# watch.net
KiCad netlist of a schematic drawn in Altium Designer
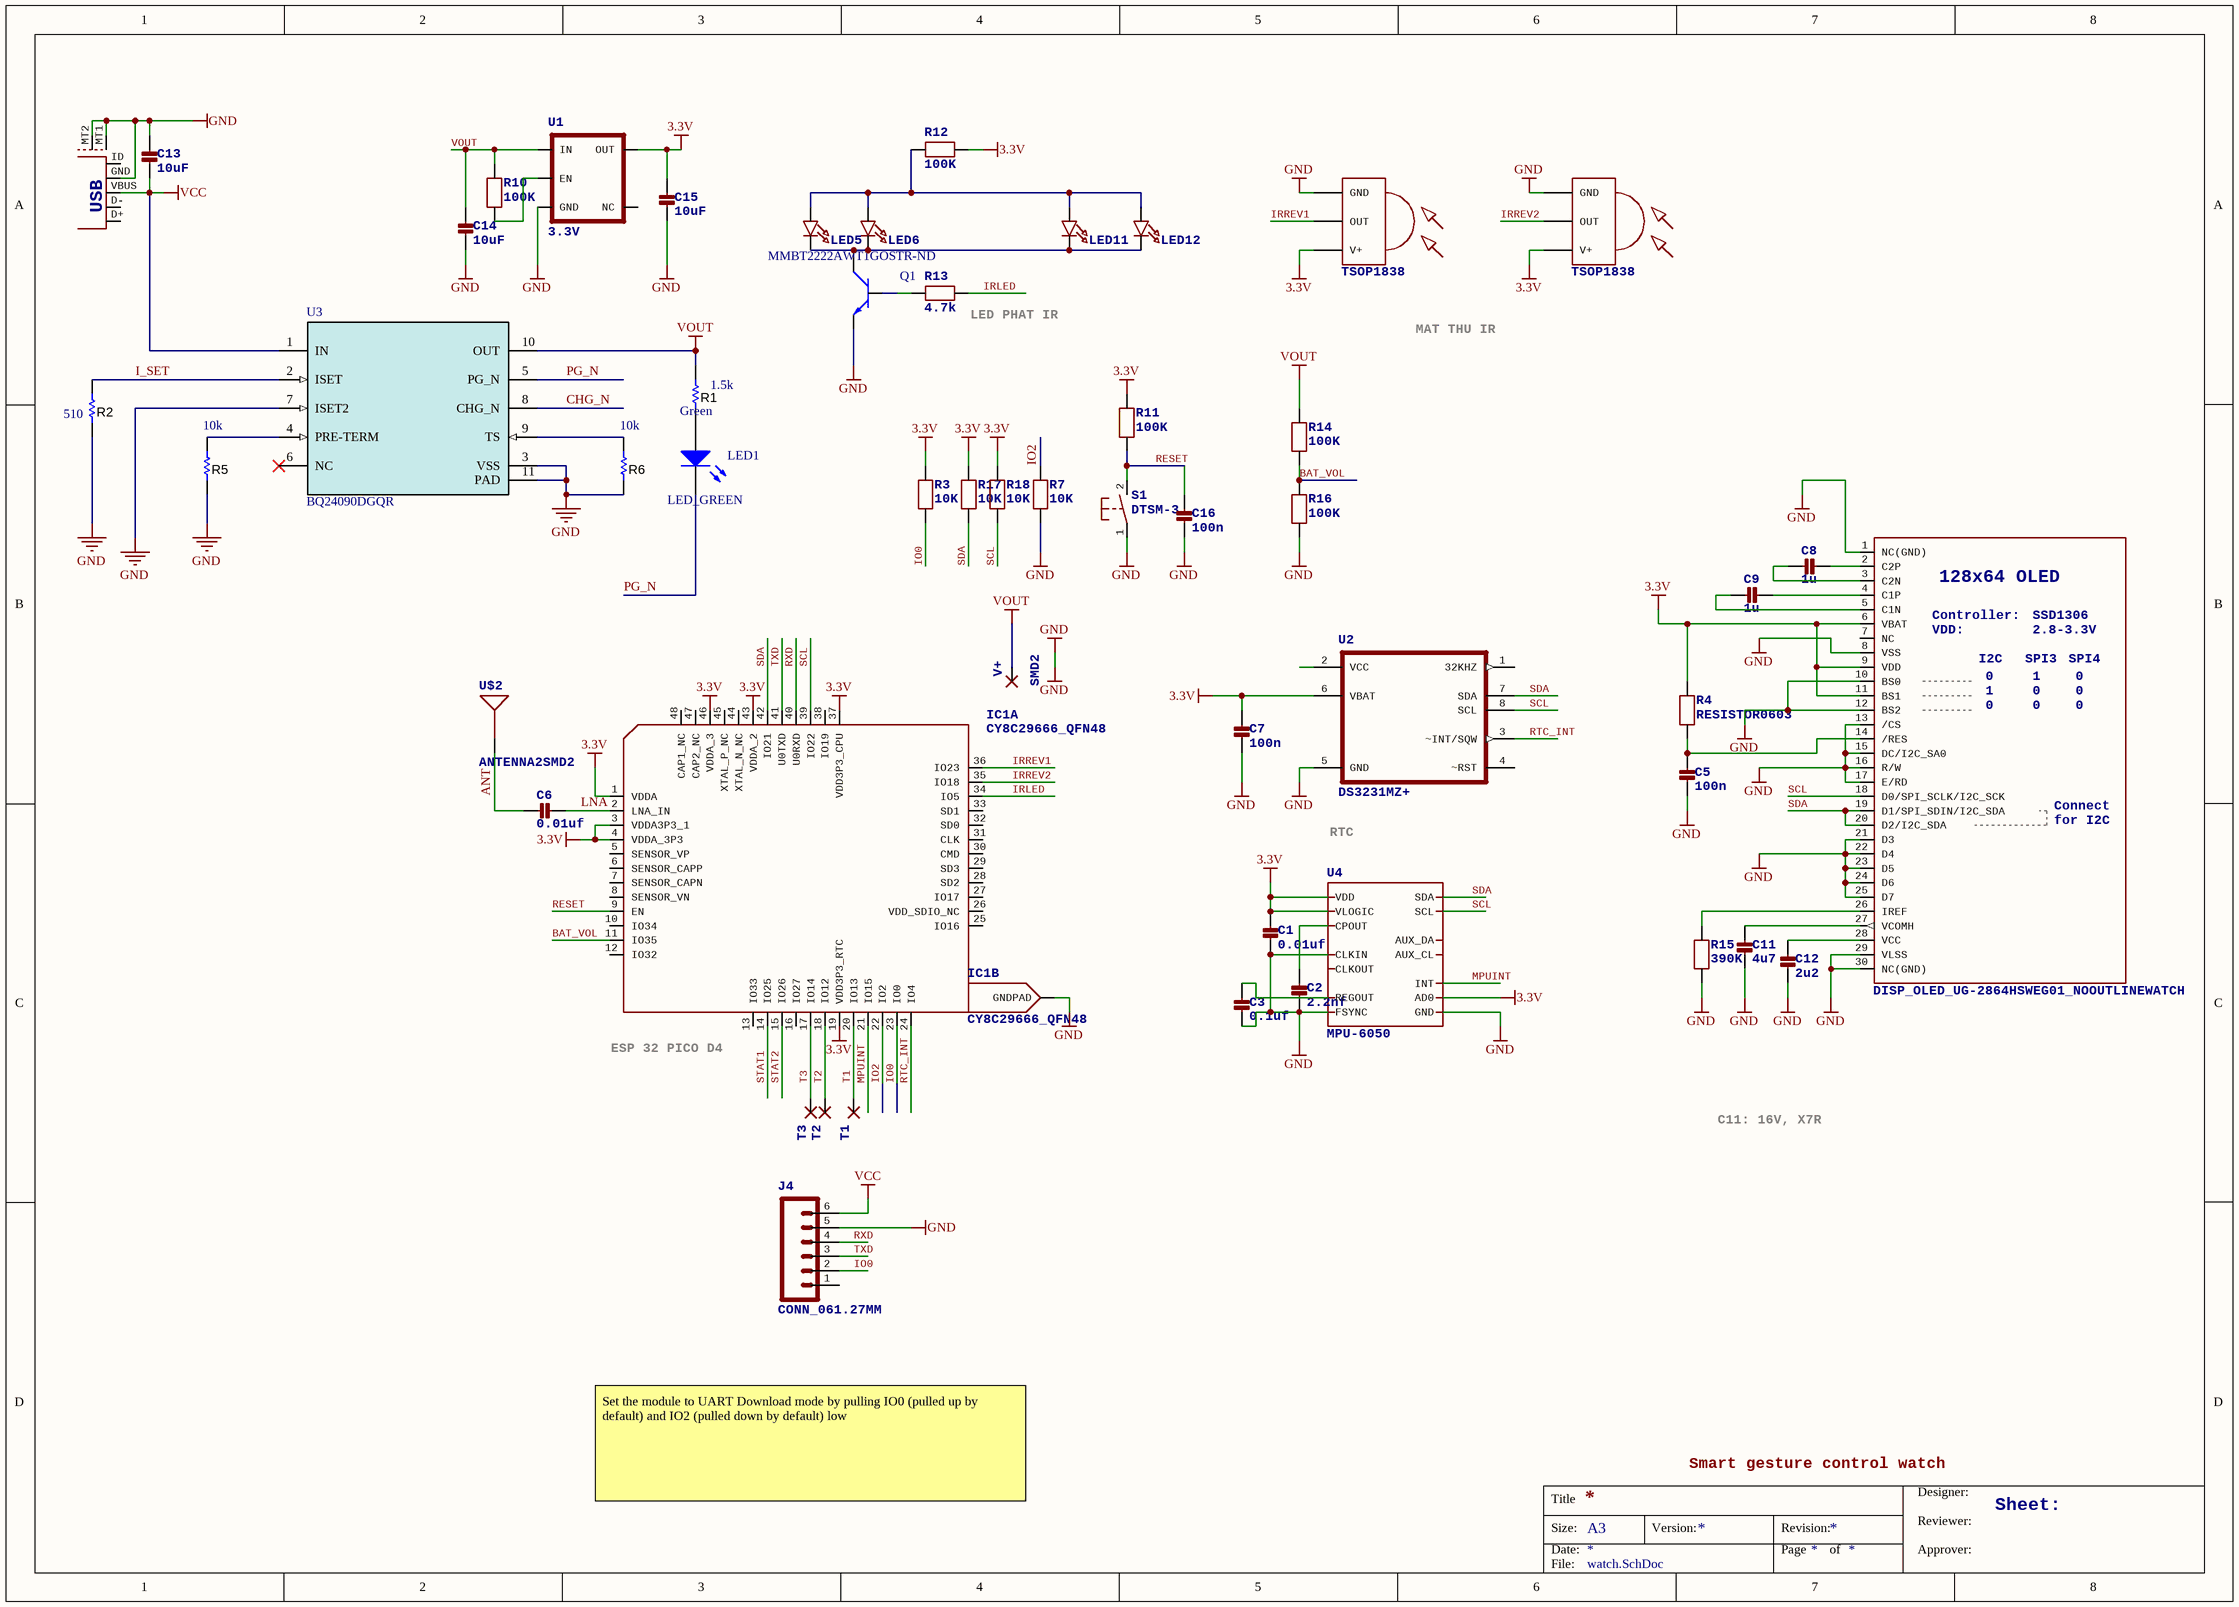
[diagram p0: watch.SchDoc]

(export (version "E")
  (design (tool "Eeschema 10.0.6"))
  (components
    (comp (ref "C1") (value "0.01uf") (footprint "0603") (libsource (lib "") (part "CAP_CERAMIC0603_2")))
    (comp (ref "C2")
      (value "2.2nf")
      (footprint "0603")
      (libsource (lib "microbuilder") (part "CAP_CERAMIC0603"))
    )
    (comp (ref "C3") (value "0.1uf") (footprint "0603") (libsource (lib "") (part "CAP_CERAMIC0603_2")))
    (comp (ref "C5")
      (value "100n")
      (footprint "0603")
      (libsource (lib "microbuilder") (part "CAP_CERAMIC0603"))
    )
    (comp (ref "C6") (value "0.01uf") (footprint "0603") (libsource (lib "") (part "CAP_CERAMIC0603_1")))
    (comp (ref "C7")
      (value "100n")
      (footprint "0603")
      (libsource (lib "microbuilder") (part "CAP_CERAMIC0603"))
    )
    (comp (ref "C8") (value "1u") (footprint "0603") (libsource (lib "") (part "CAP_CERAMIC0603_1")))
    (comp (ref "C9") (value "1u") (footprint "0603") (libsource (lib "") (part "CAP_CERAMIC0603_1")))
    (comp (ref "C11")
      (value "4u7")
      (footprint "0603")
      (libsource (lib "microbuilder") (part "CAP_CERAMIC0603"))
    )
    (comp (ref "C12")
      (value "2u2")
      (footprint "0603")
      (libsource (lib "microbuilder") (part "CAP_CERAMIC0603"))
    )
    (comp (ref "C13")
      (value "10uF")
      (footprint "0603")
      (libsource (lib "microbuilder") (part "CAP_CERAMIC0603"))
    )
    (comp (ref "C14")
      (value "10uF")
      (footprint "0603")
      (libsource (lib "microbuilder") (part "CAP_CERAMIC0603"))
    )
    (comp (ref "C15")
      (value "10uF")
      (footprint "0603")
      (libsource (lib "microbuilder") (part "CAP_CERAMIC0603"))
    )
    (comp (ref "C16")
      (value "100n")
      (footprint "0603")
      (libsource (lib "microbuilder") (part "CAP_CERAMIC0603"))
    )
    (comp (ref "IC1")
      (value "CY8C29666_QFN48")
      (footprint "QFN48")
      (libsource (lib "watch") (part "CY8C29666_QFN48"))
    )
    (comp (ref "J4")
      (value "CONN_061.27MM")
      (footprint "1X06_1.27MM")
      (libsource (lib "SparkFun-Connectors") (part "CONN_061.27MM"))
    )
    (comp (ref "LED1")
      (value "LED_GREEN")
      (footprint "led0603")
      (description "Typical INFRARED GaAs LED")
      (fields
        (field (name "MANUFACTURER") "Lite-On Inc.")
        (field (name "MANUFACTURER PART NUMBER") "LTST-C191KGKT")
        (field (name "COLOR") "Green")
      )
      (libsource (lib "BBiQ_LIB") (part "LED_GREEN"))
    )
    (comp (ref "LED5")
      (value "LED0805")
      (footprint "CHIPLED_0805")
      (libsource (lib "watch") (part "LED0805"))
    )
    (comp (ref "LED6")
      (value "LED0805")
      (footprint "CHIPLED_0805")
      (libsource (lib "watch") (part "LED0805"))
    )
    (comp (ref "LED11")
      (value "LED0805")
      (footprint "CHIPLED_0805")
      (libsource (lib "watch") (part "LED0805"))
    )
    (comp (ref "LED12")
      (value "LED0805")
      (footprint "CHIPLED_0805")
      (libsource (lib "watch") (part "LED0805"))
    )
    (comp (ref "OLED1")
      (value "DISP_OLED_UG-2864HSWEG01_NOOUTLINEWATCH")
      (footprint "UG-2864HSWEG01_1.3_WRAPAROUND_WATCH")
      (fields
        (field (name "128X64OLED") "128x64 OLED")
        (field (name "I2C") "I2C")
        (field (name "SPI3") "SPI3")
        (field (name "0") "0")
        (field (name "0_1") "0")
        (field (name "0_2") "0")
        (field (name "0_3") "0")
        (field (name "1") "1")
        (field (name "1_1") "1")
        (field (name "CONNECT") "Connect")
        (field (name "FORI2C") "for I2C")
        (field (name "CONTROLLER") "Controller:")
        (field (name "SSD1306") "SSD1306")
        (field (name "VDD") "VDD:")
        (field (name "2.8-3.3V") "2.8-3.3V")
        (field (name "SPI4") "SPI4")
        (field (name "0_4") "0")
        (field (name "0_5") "0")
        (field (name "0_6") "0")
      )
      (libsource (lib "zak") (part "DISP_OLED_UG-2864HSWEG01_NOOUTLINEWATCH"))
    )
    (comp (ref "Q1")
      (value "MMBT2222A")
      (footprint "SOT-323")
      (description "NPN switching transistor  40V 600mA SOT23")
      (fields
        (field (name "SUPPLIER PART NUMBER 1") "MMBT2222AWT1GOSTR-ND")
        (field (name "MANUFACTURER") "ON Semiconductor")
        (field (name "MANUFACTURER PART NUMBER") "MMBT2222AWT1G")
      )
      (libsource (lib "BBiQ_LIB") (part "MMBT2222A"))
    )
    (comp (ref "R1")
      (value "~")
      (footprint "0603")
      (description "RES SMD 1.5K OHM 5% 1/10W 0603")
      (fields
        (field (name "MANUFACTURER") "Yageo")
        (field (name "MANUFACTURER PART NUMBER") "RC0603JR-071K5L")
        (field (name "RESISTANCE (OHMS)") "1.5k")
      )
      (libsource (lib "BBiQ_LIB") (part "RC0603JR-071K5L"))
    )
    (comp (ref "R2")
      (value "~")
      (footprint "0603")
      (description "RES SMD 510 OHM 5% 1/10W 0603")
      (fields
        (field (name "MANUFACTURER") "Yageo")
        (field (name "MANUFACTURER PART NUMBER") "RC0603JR-07510RL")
        (field (name "RESISTANCE (OHMS)") "510")
      )
      (libsource (lib "BBiQ_LIB") (part "RC0603JR-07510RL"))
    )
    (comp (ref "R3") (value "10K") (footprint "0603") (libsource (lib "microbuilder") (part "RESISTOR0603")))
    (comp (ref "R4")
      (value "RESISTOR0603")
      (footprint "0603")
      (libsource (lib "microbuilder") (part "RESISTOR0603"))
    )
    (comp (ref "R5")
      (value "~")
      (footprint "0603")
      (description "RES SMD 10K OHM 5% 1/10W 0603")
      (fields
        (field (name "MANUFACTURER") "Yageo")
        (field (name "MANUFACTURER PART NUMBER") "RC0603JR-0710KL")
        (field (name "RESISTANCE (OHMS)") "10k")
      )
      (libsource (lib "BBiQ_LIB") (part "RC0603JR-0710KL"))
    )
    (comp (ref "R6")
      (value "~")
      (footprint "0603")
      (description "RES SMD 10K OHM 5% 1/10W 0603")
      (fields
        (field (name "MANUFACTURER") "Yageo")
        (field (name "MANUFACTURER PART NUMBER") "RC0603JR-0710KL")
        (field (name "RESISTANCE (OHMS)") "10k")
      )
      (libsource (lib "BBiQ_LIB") (part "RC0603JR-0710KL"))
    )
    (comp (ref "R7") (value "10K") (footprint "0603") (libsource (lib "microbuilder") (part "RESISTOR0603")))
    (comp (ref "R10")
      (value "100K")
      (footprint "0603")
      (libsource (lib "microbuilder") (part "RESISTOR0603"))
    )
    (comp (ref "R11")
      (value "100K")
      (footprint "0603")
      (libsource (lib "microbuilder") (part "RESISTOR0603"))
    )
    (comp (ref "R12")
      (value "100K")
      (footprint "0603")
      (libsource (lib "microbuilder") (part "RESISTOR0603"))
    )
    (comp (ref "R13")
      (value "4.7k")
      (footprint "0603")
      (libsource (lib "microbuilder") (part "RESISTOR0603"))
    )
    (comp (ref "R14")
      (value "100K")
      (footprint "0603")
      (libsource (lib "microbuilder") (part "RESISTOR0603"))
    )
    (comp (ref "R15")
      (value "390K")
      (footprint "0603")
      (libsource (lib "microbuilder") (part "RESISTOR0603"))
    )
    (comp (ref "R16")
      (value "100K")
      (footprint "0603")
      (libsource (lib "microbuilder") (part "RESISTOR0603"))
    )
    (comp (ref "R17") (value "10K") (footprint "0603") (libsource (lib "microbuilder") (part "RESISTOR0603")))
    (comp (ref "R18") (value "10K") (footprint "0603") (libsource (lib "microbuilder") (part "RESISTOR0603")))
    (comp (ref "S1") (value "DTSM-3") (footprint "DTSM-3") (libsource (lib "switch-tact") (part "DTSM-3")))
    (comp (ref "T1")
      (value "SMD2")
      (footprint "SMD1,27-2,54")
      (description "SMD PAD")
      (libsource (lib "wirepad") (part "SMD2"))
    )
    (comp (ref "T2")
      (value "SMD2")
      (footprint "SMD1,27-2,54")
      (description "SMD PAD")
      (libsource (lib "wirepad") (part "SMD2"))
    )
    (comp (ref "T3")
      (value "SMD2")
      (footprint "SMD1,27-2,54")
      (description "SMD PAD")
      (libsource (lib "wirepad") (part "SMD2"))
    )
    (comp (ref "U$2")
      (value "ANTENNA2SMD2")
      (footprint "ANTENNA-CHIP3")
      (libsource (lib "SparkFun-RF") (part "ANTENNA2SMD2"))
    )
    (comp (ref "U$3")
      (value "TSOP1838")
      (footprint "TSOP18XX")
      (description "IR Receiver and Demodulator")
      (libsource (lib "tsop-1") (part "TSOP1838"))
    )
    (comp (ref "U$4")
      (value "TSOP1838")
      (footprint "TSOP18XX")
      (description "IR Receiver and Demodulator")
      (libsource (lib "tsop-1") (part "TSOP1838"))
    )
    (comp (ref "U1")
      (value "3.3V")
      (footprint "SOT23-5")
      (libsource (lib "SparkFun-IC-Power") (part "V_REG_AP2112K-3.3V"))
    )
    (comp (ref "U2")
      (value "DS3231MZ+")
      (footprint "SOIC8_150MIL_SMPAD")
      (libsource (lib "zak") (part "DS3231MZ+SMPAD"))
    )
    (comp (ref "U3")
      (value "BQ24090DGQR")
      (footprint "DGQ0010D_NV_N")
      (description "Single Cell Li-Ion and Li-Pol Battery Charger")
      (fields (field (name "MANUFACTURER") "Texas Instruments"))
      (libsource (lib "BBiQ_LIB") (part "BQ24090DGQR"))
    )
    (comp (ref "U4")
      (value "MPU-6050")
      (footprint "QFN.24.4X4")
      (libsource (lib "invensense") (part "MPU-6050"))
    )
    (comp (ref "USB1")
      (value "USB-MICROBLARGEPAD")
      (footprint "USB-MICROB_LARGEPAD")
      (fields (field (name "USB") "USB"))
      (libsource (lib "zak") (part "USB-MICROBLARGEPAD"))
    )
    (comp (ref "V+")
      (value "SMD2")
      (footprint "SMD1,27-2,54")
      (description "SMD PAD")
      (libsource (lib "wirepad") (part "SMD2"))
    )
  )
  (nets
    (net (code "1") (name "/ANT") (class "Default")
      (node (ref "C6") (pin "1") (pinfunction "P$1_1") (pintype "passive"))
      (node (ref "U$2") (pin "FEED") (pinfunction "SIGNAL_FEED") (pintype "passive"))
    )
    (net (code "2") (name "/BAT_VOL") (class "Default")
      (node (ref "IC1") (pin "11") (pinfunction "IO35_11") (pintype "passive"))
      (node (ref "R14") (pin "2") (pinfunction "2_2") (pintype "passive"))
      (node (ref "R16") (pin "1") (pinfunction "1_1") (pintype "passive"))
    )
    (net (code "3") (name "/CHG_N") (class "Default")
      (node (ref "U3") (pin "8") (pinfunction "CHG_N_8") (pintype "tri_state"))
    )
    (net (code "4") (name "/IO0") (class "Default")
      (node (ref "IC1") (pin "23") (pinfunction "IO0_23") (pintype "passive"))
      (node (ref "J4") (pin "2") (pinfunction "2_2") (pintype "passive"))
      (node (ref "R3") (pin "2") (pinfunction "2_2") (pintype "passive"))
    )
    (net (code "5") (name "/IO2") (class "Default")
      (node (ref "IC1") (pin "22") (pinfunction "IO2_22") (pintype "passive"))
      (node (ref "R7") (pin "1") (pinfunction "1_1") (pintype "passive"))
    )
    (net (code "6") (name "/IRLED") (class "Default")
      (node (ref "IC1") (pin "34") (pinfunction "IO5_34") (pintype "passive"))
      (node (ref "R13") (pin "1") (pinfunction "1_1") (pintype "passive"))
    )
    (net (code "7") (name "/IRREV1") (class "Default")
      (node (ref "IC1") (pin "36") (pinfunction "IO23_36") (pintype "passive"))
      (node (ref "U$4") (pin "OUT") (pinfunction "OUT_OUT") (pintype "passive"))
    )
    (net (code "8") (name "/IRREV2") (class "Default")
      (node (ref "IC1") (pin "35") (pinfunction "IO18_35") (pintype "passive"))
      (node (ref "U$3") (pin "OUT") (pinfunction "OUT_OUT") (pintype "passive"))
    )
    (net (code "9") (name "/I_SET") (class "Default")
      (node (ref "R2") (pin "2") (pinfunction "2_2") (pintype "passive"))
      (node (ref "U3") (pin "2") (pinfunction "ISET_2") (pintype "input"))
    )
    (net (code "10") (name "/LNA") (class "Default")
      (node (ref "C6") (pin "2") (pinfunction "P$2_2") (pintype "passive"))
      (node (ref "IC1") (pin "2") (pinfunction "LNA_IN_2") (pintype "passive"))
    )
    (net (code "11") (name "/MPUINT") (class "Default")
      (node (ref "IC1") (pin "21") (pinfunction "IO15_21") (pintype "passive"))
      (node (ref "U4") (pin "12") (pinfunction "INT_12") (pintype "passive"))
    )
    (net (code "12") (name "/PG_N") (class "Default")
      (node (ref "LED1") (pin "2") (pinfunction "K_2") (pintype "passive"))
      (node (ref "U3") (pin "5") (pinfunction "PG_N_5") (pintype "tri_state"))
    )
    (net (code "13") (name "/RESET") (class "Default")
      (node (ref "C16") (pin "1") (pinfunction "P$1_1") (pintype "passive"))
      (node (ref "IC1") (pin "9") (pinfunction "EN_9") (pintype "passive"))
      (node (ref "R11") (pin "1") (pinfunction "1_1") (pintype "passive"))
      (node (ref "S1") (pin "2") (pinfunction "2_2") (pintype "passive"))
    )
    (net (code "14") (name "/RTC_INT") (class "Default")
      (node (ref "IC1") (pin "24") (pinfunction "IO4_24") (pintype "passive"))
      (node (ref "U2") (pin "3") (pinfunction "~INT/SQW_3") (pintype "output"))
    )
    (net (code "15") (name "/RXD") (class "Default")
      (node (ref "IC1") (pin "40") (pinfunction "U0RXD_40") (pintype "passive"))
      (node (ref "J4") (pin "4") (pinfunction "4_4") (pintype "passive"))
    )
    (net (code "16") (name "/SCL") (class "Default")
      (node (ref "IC1") (pin "39") (pinfunction "IO22_39") (pintype "passive"))
      (node (ref "OLED1") (pin "18") (pinfunction "D0/SPI_SCLK/I2C_SCK_18") (pintype "passive"))
      (node (ref "R18") (pin "2") (pinfunction "2_2") (pintype "passive"))
      (node (ref "U2") (pin "8") (pinfunction "SCL_8") (pintype "passive"))
      (node (ref "U4") (pin "23") (pinfunction "SCL_23") (pintype "passive"))
    )
    (net (code "17") (name "/SDA") (class "Default")
      (node (ref "IC1") (pin "42") (pinfunction "IO21_42") (pintype "power_in"))
      (node (ref "OLED1") (pin "19") (pinfunction "D1/SPI_SDIN/I2C_SDA_19") (pintype "passive"))
      (node (ref "OLED1") (pin "20") (pinfunction "D2/I2C_SDA_20") (pintype "passive"))
      (node (ref "R17") (pin "2") (pinfunction "2_2") (pintype "passive"))
      (node (ref "U2") (pin "7") (pinfunction "SDA_7") (pintype "passive"))
      (node (ref "U4") (pin "24") (pinfunction "SDA_24") (pintype "passive"))
    )
    (net (code "18") (name "/STAT1") (class "Default")
      (node (ref "IC1") (pin "14") (pinfunction "IO25_14") (pintype "passive"))
    )
    (net (code "19") (name "/STAT2") (class "Default")
      (node (ref "IC1") (pin "15") (pinfunction "IO26_15") (pintype "passive"))
    )
    (net (code "20") (name "/T1") (class "Default")
      (node (ref "IC1") (pin "20") (pinfunction "IO13_20") (pintype "passive"))
      (node (ref "T1") (pin "1") (pinfunction "P_1") (pintype "passive"))
    )
    (net (code "21") (name "/T2") (class "Default")
      (node (ref "IC1") (pin "18") (pinfunction "IO12_18") (pintype "power_in"))
      (node (ref "T2") (pin "1") (pinfunction "P_1") (pintype "passive"))
    )
    (net (code "22") (name "/T3") (class "Default")
      (node (ref "IC1") (pin "17") (pinfunction "IO14_17") (pintype "passive"))
      (node (ref "T3") (pin "1") (pinfunction "P_1") (pintype "passive"))
    )
    (net (code "23") (name "/TXD") (class "Default")
      (node (ref "IC1") (pin "41") (pinfunction "U0TXD_41") (pintype "passive"))
      (node (ref "J4") (pin "3") (pinfunction "3_3") (pintype "passive"))
    )
    (net (code "24") (name "3.3V") (class "Default")
      (node (ref "C1") (pin "2") (pinfunction "P$2_2") (pintype "passive"))
      (node (ref "C15") (pin "1") (pinfunction "P$1_1") (pintype "passive"))
      (node (ref "C7") (pin "1") (pinfunction "P$1_1") (pintype "passive"))
      (node (ref "IC1") (pin "1") (pinfunction "VDDA_1") (pintype "passive"))
      (node (ref "IC1") (pin "19") (pinfunction "VDD3P3_RTC_19") (pintype "passive"))
      (node (ref "IC1") (pin "3") (pinfunction "VDDA3P3_1_3") (pintype "passive"))
      (node (ref "IC1") (pin "37") (pinfunction "VDD3P3_CPU_37") (pintype "passive"))
      (node (ref "IC1") (pin "4") (pinfunction "VDDA_3P3_4") (pintype "passive"))
      (node (ref "IC1") (pin "43") (pinfunction "VDDA_2_43") (pintype "passive"))
      (node (ref "IC1") (pin "46") (pinfunction "VDDA_3_46") (pintype "passive"))
      (node (ref "OLED1") (pin "11") (pinfunction "BS1_11") (pintype "passive"))
      (node (ref "OLED1") (pin "6") (pinfunction "VBAT_6") (pintype "passive"))
      (node (ref "OLED1") (pin "9") (pinfunction "VDD_9") (pintype "power_in"))
      (node (ref "R11") (pin "2") (pinfunction "2_2") (pintype "passive"))
      (node (ref "R12") (pin "1") (pinfunction "1_1") (pintype "passive"))
      (node (ref "R17") (pin "1") (pinfunction "1_1") (pintype "passive"))
      (node (ref "R18") (pin "1") (pinfunction "1_1") (pintype "passive"))
      (node (ref "R3") (pin "1") (pinfunction "1_1") (pintype "passive"))
      (node (ref "R4") (pin "2") (pinfunction "2_2") (pintype "passive"))
      (node (ref "U$3") (pin "VCC") (pinfunction "V+_VCC") (pintype "passive"))
      (node (ref "U$4") (pin "VCC") (pinfunction "V+_VCC") (pintype "passive"))
      (node (ref "U1") (pin "5") (pinfunction "OUT_5") (pintype "passive"))
      (node (ref "U2") (pin "6") (pinfunction "VBAT_6") (pintype "power_in"))
      (node (ref "U4") (pin "13") (pinfunction "VDD_13") (pintype "passive"))
      (node (ref "U4") (pin "8") (pinfunction "VLOGIC_8") (pintype "passive"))
      (node (ref "U4") (pin "9") (pinfunction "AD0_9") (pintype "passive"))
    )
    (net (code "25") (name "GND") (class "Default")
      (node (ref "C1") (pin "1") (pinfunction "P$1_1") (pintype "passive"))
      (node (ref "C11") (pin "2") (pinfunction "P$2_2") (pintype "passive"))
      (node (ref "C12") (pin "2") (pinfunction "P$2_2") (pintype "passive"))
      (node (ref "C13") (pin "1") (pinfunction "P$1_1") (pintype "passive"))
      (node (ref "C14") (pin "2") (pinfunction "P$2_2") (pintype "passive"))
      (node (ref "C15") (pin "2") (pinfunction "P$2_2") (pintype "passive"))
      (node (ref "C16") (pin "2") (pinfunction "P$2_2") (pintype "passive"))
      (node (ref "C2") (pin "2") (pinfunction "P$2_2") (pintype "passive"))
      (node (ref "C3") (pin "1") (pinfunction "P$1_1") (pintype "passive"))
      (node (ref "C5") (pin "2") (pinfunction "P$2_2") (pintype "passive"))
      (node (ref "C7") (pin "2") (pinfunction "P$2_2") (pintype "passive"))
      (node (ref "IC1") (pin "EXP") (pinfunction "GNDPAD_EXP") (pintype "power_in"))
      (node (ref "J4") (pin "5") (pinfunction "5_5") (pintype "passive"))
      (node (ref "OLED1") (pin "1") (pinfunction "NC(GND)_1") (pintype "passive"))
      (node (ref "OLED1") (pin "10") (pinfunction "BS0_10") (pintype "passive"))
      (node (ref "OLED1") (pin "12") (pinfunction "BS2_12") (pintype "passive"))
      (node (ref "OLED1") (pin "13") (pinfunction "/CS_13") (pintype "passive"))
      (node (ref "OLED1") (pin "15") (pinfunction "DC/I2C_SA0_15") (pintype "passive"))
      (node (ref "OLED1") (pin "16") (pinfunction "R/W_16") (pintype "passive"))
      (node (ref "OLED1") (pin "17") (pinfunction "E/RD_17") (pintype "passive"))
      (node (ref "OLED1") (pin "21") (pinfunction "D3_21") (pintype "passive"))
      (node (ref "OLED1") (pin "22") (pinfunction "D4_22") (pintype "passive"))
      (node (ref "OLED1") (pin "23") (pinfunction "D5_23") (pintype "passive"))
      (node (ref "OLED1") (pin "24") (pinfunction "D6_24") (pintype "passive"))
      (node (ref "OLED1") (pin "25") (pinfunction "D7_25") (pintype "passive"))
      (node (ref "OLED1") (pin "29") (pinfunction "VLSS_29") (pintype "power_in"))
      (node (ref "OLED1") (pin "30") (pinfunction "NC(GND)_30") (pintype "passive"))
      (node (ref "OLED1") (pin "8") (pinfunction "VSS_8") (pintype "power_in"))
      (node (ref "Q1") (pin "2") (pinfunction "E_2") (pintype "passive"))
      (node (ref "R15") (pin "1") (pinfunction "1_1") (pintype "passive"))
      (node (ref "R16") (pin "2") (pinfunction "2_2") (pintype "passive"))
      (node (ref "R2") (pin "1") (pinfunction "1_1") (pintype "passive"))
      (node (ref "R5") (pin "1") (pinfunction "1_1") (pintype "passive"))
      (node (ref "R6") (pin "1") (pinfunction "1_1") (pintype "passive"))
      (node (ref "R7") (pin "2") (pinfunction "2_2") (pintype "passive"))
      (node (ref "S1") (pin "1") (pinfunction "1_1") (pintype "passive"))
      (node (ref "U$3") (pin "GND") (pinfunction "GND_GND") (pintype "passive"))
      (node (ref "U$4") (pin "GND") (pinfunction "GND_GND") (pintype "passive"))
      (node (ref "U1") (pin "2") (pinfunction "GND_2") (pintype "passive"))
      (node (ref "U2") (pin "5") (pinfunction "GND_5") (pintype "passive"))
      (node (ref "U3") (pin "11") (pinfunction "PAD_11") (pintype "power_in"))
      (node (ref "U3") (pin "3") (pinfunction "VSS_3") (pintype "power_in"))
      (node (ref "U3") (pin "7") (pinfunction "ISET2_7") (pintype "input"))
      (node (ref "U4") (pin "1") (pinfunction "CLKIN_1") (pintype "passive"))
      (node (ref "U4") (pin "11") (pinfunction "FSYNC_11") (pintype "passive"))
      (node (ref "U4") (pin "18") (pinfunction "GND_18") (pintype "passive"))
      (node (ref "USB1") (pin "GND") (pinfunction "GND_GND") (pintype "passive"))
      (node (ref "USB1") (pin "MT1") (pinfunction "SHEILD1_MT1") (pintype "passive"))
      (node (ref "USB1") (pin "MT2") (pinfunction "SHEILD2_MT2") (pintype "passive"))
    )
    (net (code "26") (name "Net-(C2-P$1)") (class "Default")
      (node (ref "C2") (pin "1") (pinfunction "P$1_1") (pintype "passive"))
      (node (ref "U4") (pin "20") (pinfunction "CPOUT_20") (pintype "passive"))
    )
    (net (code "27") (name "Net-(C3-P$2)") (class "Default")
      (node (ref "C3") (pin "2") (pinfunction "P$2_2") (pintype "passive"))
      (node (ref "U4") (pin "10") (pinfunction "REGOUT_10") (pintype "passive"))
    )
    (net (code "28") (name "Net-(C5-P$1)") (class "Default")
      (node (ref "C5") (pin "1") (pinfunction "P$1_1") (pintype "passive"))
      (node (ref "OLED1") (pin "14") (pinfunction "/RES_14") (pintype "passive"))
      (node (ref "R4") (pin "1") (pinfunction "1_1") (pintype "passive"))
    )
    (net (code "29") (name "Net-(C8-P$1)") (class "Default")
      (node (ref "C8") (pin "1") (pinfunction "P$1_1") (pintype "passive"))
      (node (ref "OLED1") (pin "3") (pinfunction "C2N_3") (pintype "passive"))
    )
    (net (code "30") (name "Net-(C8-P$2)") (class "Default")
      (node (ref "C8") (pin "2") (pinfunction "P$2_2") (pintype "passive"))
      (node (ref "OLED1") (pin "2") (pinfunction "C2P_2") (pintype "passive"))
    )
    (net (code "31") (name "Net-(C9-P$1)") (class "Default")
      (node (ref "C9") (pin "1") (pinfunction "P$1_1") (pintype "passive"))
      (node (ref "OLED1") (pin "5") (pinfunction "C1N_5") (pintype "passive"))
    )
    (net (code "32") (name "Net-(C9-P$2)") (class "Default")
      (node (ref "C9") (pin "2") (pinfunction "P$2_2") (pintype "passive"))
      (node (ref "OLED1") (pin "4") (pinfunction "C1P_4") (pintype "passive"))
    )
    (net (code "33") (name "Net-(C11-P$1)") (class "Default")
      (node (ref "C11") (pin "1") (pinfunction "P$1_1") (pintype "passive"))
      (node (ref "OLED1") (pin "27") (pinfunction "VCOMH_27") (pintype "output"))
    )
    (net (code "34") (name "Net-(C12-P$1)") (class "Default")
      (node (ref "C12") (pin "1") (pinfunction "P$1_1") (pintype "passive"))
      (node (ref "OLED1") (pin "28") (pinfunction "VCC_28") (pintype "power_in"))
    )
    (net (code "35") (name "Net-(LED1-A)") (class "Default")
      (node (ref "LED1") (pin "1") (pinfunction "A_1") (pintype "passive"))
      (node (ref "R1") (pin "1") (pinfunction "1_1") (pintype "passive"))
    )
    (net (code "36") (name "Net-(LED11-A)") (class "Default")
      (node (ref "LED11") (pin "1") (pinfunction "A_1") (pintype "passive"))
      (node (ref "LED12") (pin "1") (pinfunction "A_1") (pintype "passive"))
      (node (ref "LED5") (pin "1") (pinfunction "A_1") (pintype "passive"))
      (node (ref "LED6") (pin "1") (pinfunction "A_1") (pintype "passive"))
      (node (ref "R12") (pin "2") (pinfunction "2_2") (pintype "passive"))
    )
    (net (code "37") (name "Net-(LED11-C)") (class "Default")
      (node (ref "LED11") (pin "2") (pinfunction "C_2") (pintype "passive"))
      (node (ref "LED12") (pin "2") (pinfunction "C_2") (pintype "passive"))
      (node (ref "LED5") (pin "2") (pinfunction "C_2") (pintype "passive"))
      (node (ref "LED6") (pin "2") (pinfunction "C_2") (pintype "passive"))
      (node (ref "Q1") (pin "3") (pinfunction "C_3") (pintype "passive"))
    )
    (net (code "38") (name "Net-(OLED1-IREF)") (class "Default")
      (node (ref "OLED1") (pin "26") (pinfunction "IREF_26") (pintype "passive"))
      (node (ref "R15") (pin "2") (pinfunction "2_2") (pintype "passive"))
    )
    (net (code "39") (name "Net-(Q1-B)") (class "Default")
      (node (ref "Q1") (pin "1") (pinfunction "B_1") (pintype "passive"))
      (node (ref "R13") (pin "2") (pinfunction "2_2") (pintype "passive"))
    )
    (net (code "40") (name "Net-(U1-EN)") (class "Default")
      (node (ref "R10") (pin "1") (pinfunction "1_1") (pintype "passive"))
      (node (ref "U1") (pin "3") (pinfunction "EN_3") (pintype "passive"))
    )
    (net (code "41") (name "Net-(U3-PRE-TERM)") (class "Default")
      (node (ref "R5") (pin "2") (pinfunction "2_2") (pintype "passive"))
      (node (ref "U3") (pin "4") (pinfunction "PRE-TERM_4") (pintype "input"))
    )
    (net (code "42") (name "Net-(U3-TS)") (class "Default")
      (node (ref "R6") (pin "2") (pinfunction "2_2") (pintype "passive"))
      (node (ref "U3") (pin "9") (pinfunction "TS_9") (pintype "input"))
    )
    (net (code "43") (name "VCC") (class "Default")
      (node (ref "C13") (pin "2") (pinfunction "P$2_2") (pintype "passive"))
      (node (ref "J4") (pin "6") (pinfunction "6_6") (pintype "passive"))
      (node (ref "U3") (pin "1") (pinfunction "IN_1") (pintype "power_in"))
      (node (ref "USB1") (pin "VBUS") (pinfunction "VBUS_VBUS") (pintype "passive"))
    )
    (net (code "44") (name "VOUT") (class "Default")
      (node (ref "C14") (pin "1") (pinfunction "P$1_1") (pintype "passive"))
      (node (ref "R1") (pin "2") (pinfunction "2_2") (pintype "passive"))
      (node (ref "R10") (pin "2") (pinfunction "2_2") (pintype "passive"))
      (node (ref "R14") (pin "1") (pinfunction "1_1") (pintype "passive"))
      (node (ref "U1") (pin "1") (pinfunction "IN_1") (pintype "passive"))
      (node (ref "U3") (pin "10") (pinfunction "OUT_10") (pintype "power_in"))
      (node (ref "V+") (pin "1") (pinfunction "P_1") (pintype "passive"))
    )
    (net (code "45") (name "unconnected-(IC1A-CAP1_NC-Pad48)") (class "Default")
      (node (ref "IC1") (pin "48") (pinfunction "CAP1_NC_48") (pintype "passive"))
    )
    (net (code "46") (name "unconnected-(IC1A-CAP2_NC-Pad47)") (class "Default")
      (node (ref "IC1") (pin "47") (pinfunction "CAP2_NC_47") (pintype "passive"))
    )
    (net (code "47") (name "unconnected-(IC1A-CLK-Pad31)") (class "Default")
      (node (ref "IC1") (pin "31") (pinfunction "CLK_31") (pintype "passive"))
    )
    (net (code "48") (name "unconnected-(IC1A-CMD-Pad30)") (class "Default")
      (node (ref "IC1") (pin "30") (pinfunction "CMD_30") (pintype "passive"))
    )
    (net (code "49") (name "unconnected-(IC1A-IO16-Pad25)") (class "Default")
      (node (ref "IC1") (pin "25") (pinfunction "IO16_25") (pintype "passive"))
    )
    (net (code "50") (name "unconnected-(IC1A-IO17-Pad27)") (class "Default")
      (node (ref "IC1") (pin "27") (pinfunction "IO17_27") (pintype "passive"))
    )
    (net (code "51") (name "unconnected-(IC1A-IO19-Pad38)") (class "Default")
      (node (ref "IC1") (pin "38") (pinfunction "IO19_38") (pintype "passive"))
    )
    (net (code "52") (name "unconnected-(IC1A-IO27-Pad16)") (class "Default")
      (node (ref "IC1") (pin "16") (pinfunction "IO27_16") (pintype "passive"))
    )
    (net (code "53") (name "unconnected-(IC1A-IO32-Pad12)") (class "Default")
      (node (ref "IC1") (pin "12") (pinfunction "IO32_12") (pintype "passive"))
    )
    (net (code "54") (name "unconnected-(IC1A-IO33-Pad13)") (class "Default")
      (node (ref "IC1") (pin "13") (pinfunction "IO33_13") (pintype "passive"))
    )
    (net (code "55") (name "unconnected-(IC1A-IO34-Pad10)") (class "Default")
      (node (ref "IC1") (pin "10") (pinfunction "IO34_10") (pintype "passive"))
    )
    (net (code "56") (name "unconnected-(IC1A-SD0-Pad32)") (class "Default")
      (node (ref "IC1") (pin "32") (pinfunction "SD0_32") (pintype "passive"))
    )
    (net (code "57") (name "unconnected-(IC1A-SD1-Pad33)") (class "Default")
      (node (ref "IC1") (pin "33") (pinfunction "SD1_33") (pintype "passive"))
    )
    (net (code "58") (name "unconnected-(IC1A-SD2-Pad28)") (class "Default")
      (node (ref "IC1") (pin "28") (pinfunction "SD2_28") (pintype "passive"))
    )
    (net (code "59") (name "unconnected-(IC1A-SD3-Pad29)") (class "Default")
      (node (ref "IC1") (pin "29") (pinfunction "SD3_29") (pintype "passive"))
    )
    (net (code "60") (name "unconnected-(IC1A-SENSOR_CAPN-Pad7)") (class "Default")
      (node (ref "IC1") (pin "7") (pinfunction "SENSOR_CAPN_7") (pintype "power_in"))
    )
    (net (code "61") (name "unconnected-(IC1A-SENSOR_CAPP-Pad6)") (class "Default")
      (node (ref "IC1") (pin "6") (pinfunction "SENSOR_CAPP_6") (pintype "passive"))
    )
    (net (code "62") (name "unconnected-(IC1A-SENSOR_VN-Pad8)") (class "Default")
      (node (ref "IC1") (pin "8") (pinfunction "SENSOR_VN_8") (pintype "passive"))
    )
    (net (code "63") (name "unconnected-(IC1A-SENSOR_VP-Pad5)") (class "Default")
      (node (ref "IC1") (pin "5") (pinfunction "SENSOR_VP_5") (pintype "passive"))
    )
    (net (code "64") (name "unconnected-(IC1A-VDD_SDIO_NC-Pad26)") (class "Default")
      (node (ref "IC1") (pin "26") (pinfunction "VDD_SDIO_NC_26") (pintype "passive"))
    )
    (net (code "65") (name "unconnected-(IC1A-XTAL_N_NC-Pad44)") (class "Default")
      (node (ref "IC1") (pin "44") (pinfunction "XTAL_N_NC_44") (pintype "passive"))
    )
    (net (code "66") (name "unconnected-(IC1A-XTAL_P_NC-Pad45)") (class "Default")
      (node (ref "IC1") (pin "45") (pinfunction "XTAL_P_NC_45") (pintype "passive"))
    )
    (net (code "67") (name "unconnected-(J4-Pad1)") (class "Default")
      (node (ref "J4") (pin "1") (pinfunction "1_1") (pintype "passive"))
    )
    (net (code "68") (name "unconnected-(OLED1-NC-Pad7)") (class "Default")
      (node (ref "OLED1") (pin "7") (pinfunction "NC_7") (pintype "passive"))
    )
    (net (code "69") (name "unconnected-(U1-NC-Pad4)") (class "Default")
      (node (ref "U1") (pin "4") (pinfunction "NC_4") (pintype "passive"))
    )
    (net (code "70") (name "unconnected-(U2-32KHZ-Pad1)") (class "Default")
      (node (ref "U2") (pin "1") (pinfunction "32KHZ_1") (pintype "output"))
    )
    (net (code "71") (name "unconnected-(U2-VCC-Pad2)") (class "Default")
      (node (ref "U2") (pin "2") (pinfunction "VCC_2") (pintype "power_in"))
    )
    (net (code "72") (name "unconnected-(U2-~RST-Pad4)") (class "Default")
      (node (ref "U2") (pin "4") (pinfunction "~RST_4") (pintype "passive"))
    )
    (net (code "73") (name "unconnected-(U3-NC-Pad6)") (class "Default")
      (node (ref "U3") (pin "6") (pinfunction "NC_6") (pintype "passive+no_connect"))
    )
    (net (code "74") (name "unconnected-(U4-AUX_CL-Pad7)") (class "Default")
      (node (ref "U4") (pin "7") (pinfunction "AUX_CL_7") (pintype "passive"))
    )
    (net (code "75") (name "unconnected-(U4-AUX_DA-Pad6)") (class "Default")
      (node (ref "U4") (pin "6") (pinfunction "AUX_DA_6") (pintype "passive"))
    )
    (net (code "76") (name "unconnected-(U4-CLKOUT-Pad22)") (class "Default")
      (node (ref "U4") (pin "22") (pinfunction "CLKOUT_22") (pintype "passive"))
    )
    (net (code "77") (name "unconnected-(USB1-PadD+)") (class "Default")
      (node (ref "USB1") (pin "D+") (pinfunction "D+_D+") (pintype "passive"))
    )
    (net (code "78") (name "unconnected-(USB1-PadD-)") (class "Default")
      (node (ref "USB1") (pin "D-") (pinfunction "D-_D-") (pintype "passive"))
    )
    (net (code "79") (name "unconnected-(USB1-PadID)") (class "Default")
      (node (ref "USB1") (pin "ID") (pinfunction "ID_ID") (pintype "passive"))
    )
  )
)
